# larrow.net
KiCad netlist of a schematic drawn in EAGLE
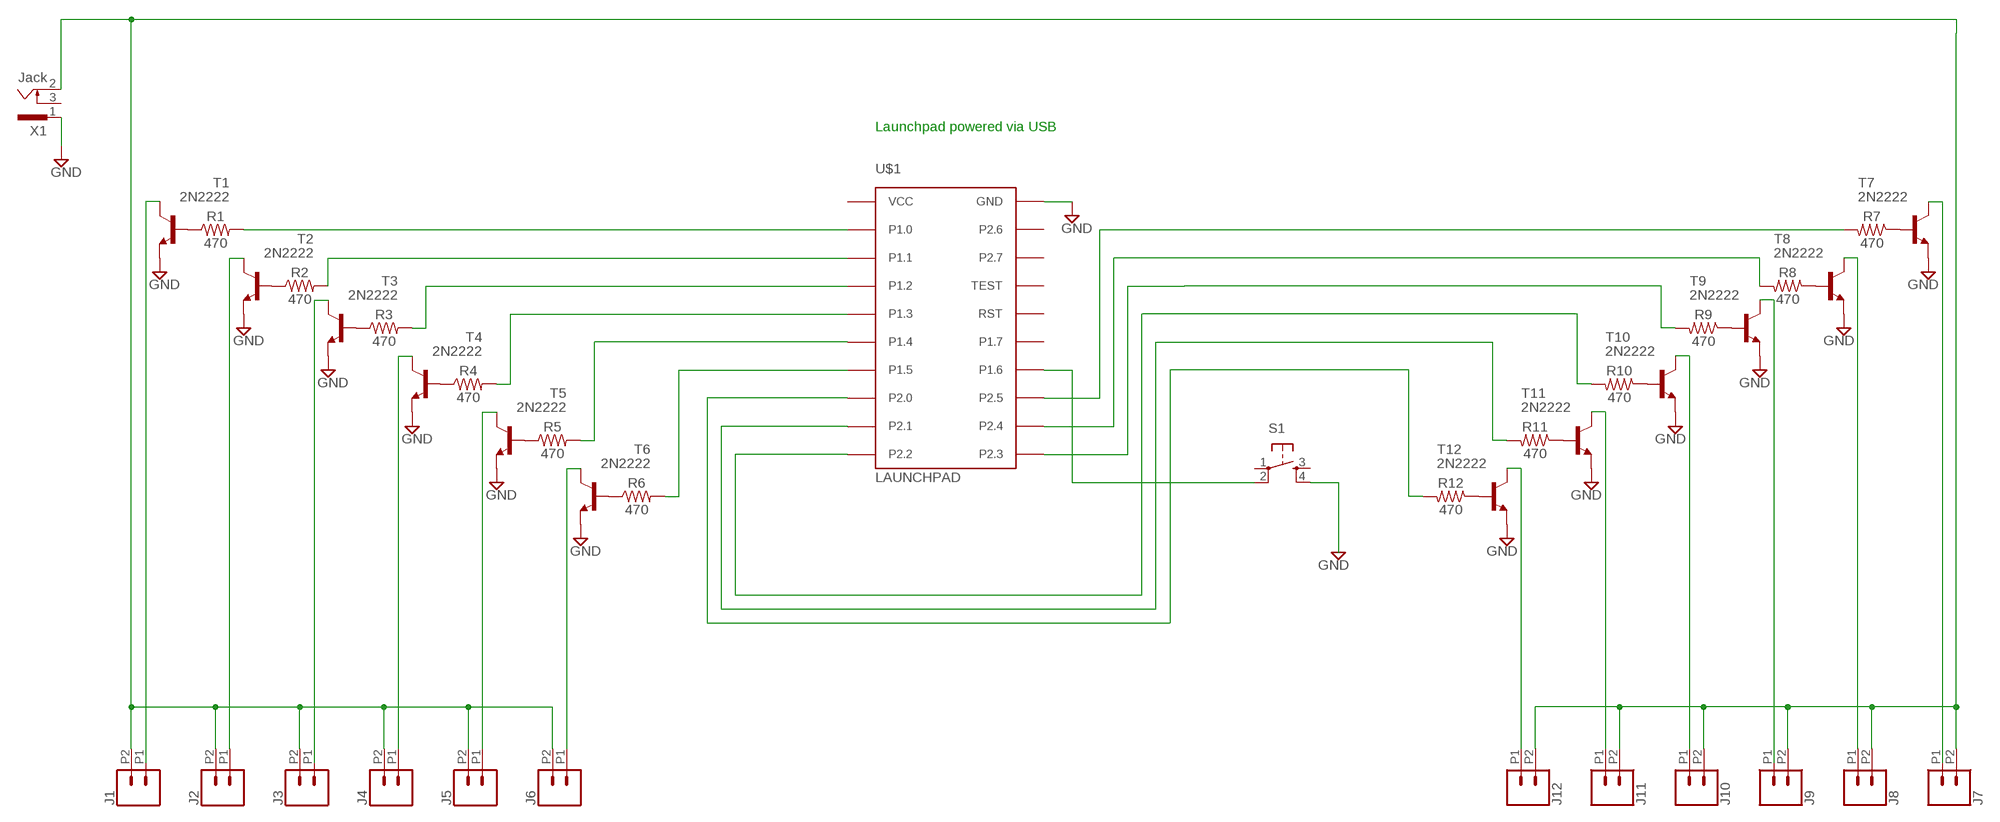
[diagram p0: schematic, sheet 1]

(export (version "E")
  (design (tool "Eeschema 10.0.6"))
  (components
    (comp (ref "J1")
      (value "CONN_022.54MM_SCREWTERM")
      (footprint "eagle-import:1X02_2.54_SCREWTERM")
      (libsource (lib "eagle-import") (part "CONN_022.54MM_SCREWTERM"))
    )
    (comp (ref "J2")
      (value "CONN_022.54MM_SCREWTERM")
      (footprint "eagle-import:1X02_2.54_SCREWTERM")
      (libsource (lib "eagle-import") (part "CONN_022.54MM_SCREWTERM"))
    )
    (comp (ref "J3")
      (value "CONN_022.54MM_SCREWTERM")
      (footprint "eagle-import:1X02_2.54_SCREWTERM")
      (libsource (lib "eagle-import") (part "CONN_022.54MM_SCREWTERM"))
    )
    (comp (ref "J4")
      (value "CONN_022.54MM_SCREWTERM")
      (footprint "eagle-import:1X02_2.54_SCREWTERM")
      (libsource (lib "eagle-import") (part "CONN_022.54MM_SCREWTERM"))
    )
    (comp (ref "J5")
      (value "CONN_022.54MM_SCREWTERM")
      (footprint "eagle-import:1X02_2.54_SCREWTERM")
      (libsource (lib "eagle-import") (part "CONN_022.54MM_SCREWTERM"))
    )
    (comp (ref "J6")
      (value "CONN_022.54MM_SCREWTERM")
      (footprint "eagle-import:1X02_2.54_SCREWTERM")
      (libsource (lib "eagle-import") (part "CONN_022.54MM_SCREWTERM"))
    )
    (comp (ref "J7")
      (value "CONN_022.54MM_SCREWTERM")
      (footprint "eagle-import:1X02_2.54_SCREWTERM")
      (libsource (lib "eagle-import") (part "CONN_022.54MM_SCREWTERM"))
    )
    (comp (ref "J8")
      (value "CONN_022.54MM_SCREWTERM")
      (footprint "eagle-import:1X02_2.54_SCREWTERM")
      (libsource (lib "eagle-import") (part "CONN_022.54MM_SCREWTERM"))
    )
    (comp (ref "J9")
      (value "CONN_022.54MM_SCREWTERM")
      (footprint "eagle-import:1X02_2.54_SCREWTERM")
      (libsource (lib "eagle-import") (part "CONN_022.54MM_SCREWTERM"))
    )
    (comp (ref "J10")
      (value "CONN_022.54MM_SCREWTERM")
      (footprint "eagle-import:1X02_2.54_SCREWTERM")
      (libsource (lib "eagle-import") (part "CONN_022.54MM_SCREWTERM"))
    )
    (comp (ref "J11")
      (value "CONN_022.54MM_SCREWTERM")
      (footprint "eagle-import:1X02_2.54_SCREWTERM")
      (libsource (lib "eagle-import") (part "CONN_022.54MM_SCREWTERM"))
    )
    (comp (ref "J12")
      (value "CONN_022.54MM_SCREWTERM")
      (footprint "eagle-import:1X02_2.54_SCREWTERM")
      (libsource (lib "eagle-import") (part "CONN_022.54MM_SCREWTERM"))
    )
    (comp (ref "R1")
      (value "470")
      (footprint "eagle-import:AXIAL-0.3")
      (libsource (lib "eagle-import") (part "1KOHM-HORIZ-1/4W-1%"))
    )
    (comp (ref "R2")
      (value "470")
      (footprint "eagle-import:AXIAL-0.3")
      (libsource (lib "eagle-import") (part "1KOHM-HORIZ-1/4W-1%"))
    )
    (comp (ref "R3")
      (value "470")
      (footprint "eagle-import:AXIAL-0.3")
      (libsource (lib "eagle-import") (part "1KOHM-HORIZ-1/4W-1%"))
    )
    (comp (ref "R4")
      (value "470")
      (footprint "eagle-import:AXIAL-0.3")
      (libsource (lib "eagle-import") (part "1KOHM-HORIZ-1/4W-1%"))
    )
    (comp (ref "R5")
      (value "470")
      (footprint "eagle-import:AXIAL-0.3")
      (libsource (lib "eagle-import") (part "1KOHM-HORIZ-1/4W-1%"))
    )
    (comp (ref "R6")
      (value "470")
      (footprint "eagle-import:AXIAL-0.3")
      (libsource (lib "eagle-import") (part "1KOHM-HORIZ-1/4W-1%"))
    )
    (comp (ref "R7")
      (value "470")
      (footprint "eagle-import:AXIAL-0.3")
      (libsource (lib "eagle-import") (part "1KOHM-HORIZ-1/4W-1%"))
    )
    (comp (ref "R8")
      (value "470")
      (footprint "eagle-import:AXIAL-0.3")
      (libsource (lib "eagle-import") (part "1KOHM-HORIZ-1/4W-1%"))
    )
    (comp (ref "R9")
      (value "470")
      (footprint "eagle-import:AXIAL-0.3")
      (libsource (lib "eagle-import") (part "1KOHM-HORIZ-1/4W-1%"))
    )
    (comp (ref "R10")
      (value "470")
      (footprint "eagle-import:AXIAL-0.3")
      (libsource (lib "eagle-import") (part "1KOHM-HORIZ-1/4W-1%"))
    )
    (comp (ref "R11")
      (value "470")
      (footprint "eagle-import:AXIAL-0.3")
      (libsource (lib "eagle-import") (part "1KOHM-HORIZ-1/4W-1%"))
    )
    (comp (ref "R12")
      (value "470")
      (footprint "eagle-import:AXIAL-0.3")
      (libsource (lib "eagle-import") (part "1KOHM-HORIZ-1/4W-1%"))
    )
    (comp (ref "S1")
      (value "TAC_SWITCHPTH")
      (footprint "eagle-import:TACTILE-PTH")
      (libsource (lib "eagle-import") (part "TAC_SWITCHPTH"))
    )
    (comp (ref "T1")
      (value "2N2222")
      (footprint "eagle-import:TO92-EBC-OVAL")
      (libsource (lib "eagle-import") (part "2N2222"))
    )
    (comp (ref "T2")
      (value "2N2222")
      (footprint "eagle-import:TO92-EBC-OVAL")
      (libsource (lib "eagle-import") (part "2N2222"))
    )
    (comp (ref "T3")
      (value "2N2222")
      (footprint "eagle-import:TO92-EBC-OVAL")
      (libsource (lib "eagle-import") (part "2N2222"))
    )
    (comp (ref "T4")
      (value "2N2222")
      (footprint "eagle-import:TO92-EBC-OVAL")
      (libsource (lib "eagle-import") (part "2N2222"))
    )
    (comp (ref "T5")
      (value "2N2222")
      (footprint "eagle-import:TO92-EBC-OVAL")
      (libsource (lib "eagle-import") (part "2N2222"))
    )
    (comp (ref "T6")
      (value "2N2222")
      (footprint "eagle-import:TO92-EBC-OVAL")
      (libsource (lib "eagle-import") (part "2N2222"))
    )
    (comp (ref "T7")
      (value "2N2222")
      (footprint "eagle-import:TO92-EBC-OVAL")
      (libsource (lib "eagle-import") (part "2N2222"))
    )
    (comp (ref "T8")
      (value "2N2222")
      (footprint "eagle-import:TO92-EBC-OVAL")
      (libsource (lib "eagle-import") (part "2N2222"))
    )
    (comp (ref "T9")
      (value "2N2222")
      (footprint "eagle-import:TO92-EBC-OVAL")
      (libsource (lib "eagle-import") (part "2N2222"))
    )
    (comp (ref "T10")
      (value "2N2222")
      (footprint "eagle-import:TO92-EBC-OVAL")
      (libsource (lib "eagle-import") (part "2N2222"))
    )
    (comp (ref "T11")
      (value "2N2222")
      (footprint "eagle-import:TO92-EBC-OVAL")
      (libsource (lib "eagle-import") (part "2N2222"))
    )
    (comp (ref "T12")
      (value "2N2222")
      (footprint "eagle-import:TO92-EBC-OVAL")
      (libsource (lib "eagle-import") (part "2N2222"))
    )
    (comp (ref "U$1")
      (value "LAUNCHPAD")
      (footprint "eagle-import:LAUNCHPAD")
      (libsource (lib "eagle-import") (part "LAUNCHPAD"))
    )
    (comp (ref "X1")
      (value "Jack")
      (footprint "eagle-import:SCD-014-A")
      (libsource (lib "eagle-import") (part "SCD-014A"))
    )
  )
  (nets
    (net (code "1") (name "/VCC") (class "Default")
      (node (ref "U$1") (pin "VCC") (pinfunction "VCC_VCC") (pintype "power_in"))
    )
    (net (code "2") (name "GND") (class "Default")
      (node (ref "S1") (pin "4") (pinfunction "4_4") (pintype "passive"))
      (node (ref "T1") (pin "E") (pinfunction "E_E") (pintype "passive"))
      (node (ref "T10") (pin "E") (pinfunction "E_E") (pintype "passive"))
      (node (ref "T11") (pin "E") (pinfunction "E_E") (pintype "passive"))
      (node (ref "T12") (pin "E") (pinfunction "E_E") (pintype "passive"))
      (node (ref "T2") (pin "E") (pinfunction "E_E") (pintype "passive"))
      (node (ref "T3") (pin "E") (pinfunction "E_E") (pintype "passive"))
      (node (ref "T4") (pin "E") (pinfunction "E_E") (pintype "passive"))
      (node (ref "T5") (pin "E") (pinfunction "E_E") (pintype "passive"))
      (node (ref "T6") (pin "E") (pinfunction "E_E") (pintype "passive"))
      (node (ref "T7") (pin "E") (pinfunction "E_E") (pintype "passive"))
      (node (ref "T8") (pin "E") (pinfunction "E_E") (pintype "passive"))
      (node (ref "T9") (pin "E") (pinfunction "E_E") (pintype "passive"))
      (node (ref "U$1") (pin "GND") (pinfunction "GND_GND") (pintype "power_in"))
      (node (ref "X1") (pin "1") (pinfunction "1_1") (pintype "passive"))
    )
    (net (code "3") (name "Net-(J1-1)") (class "Default")
      (node (ref "J1") (pin "P1") (pinfunction "1_P1") (pintype "passive"))
      (node (ref "T1") (pin "C") (pinfunction "C_C") (pintype "passive"))
    )
    (net (code "4") (name "Net-(J1-2)") (class "Default")
      (node (ref "J1") (pin "P2") (pinfunction "2_P2") (pintype "passive"))
      (node (ref "J10") (pin "P2") (pinfunction "2_P2") (pintype "passive"))
      (node (ref "J11") (pin "P2") (pinfunction "2_P2") (pintype "passive"))
      (node (ref "J12") (pin "P2") (pinfunction "2_P2") (pintype "passive"))
      (node (ref "J2") (pin "P2") (pinfunction "2_P2") (pintype "passive"))
      (node (ref "J3") (pin "P2") (pinfunction "2_P2") (pintype "passive"))
      (node (ref "J4") (pin "P2") (pinfunction "2_P2") (pintype "passive"))
      (node (ref "J5") (pin "P2") (pinfunction "2_P2") (pintype "passive"))
      (node (ref "J6") (pin "P2") (pinfunction "2_P2") (pintype "passive"))
      (node (ref "J7") (pin "P2") (pinfunction "2_P2") (pintype "passive"))
      (node (ref "J8") (pin "P2") (pinfunction "2_P2") (pintype "passive"))
      (node (ref "J9") (pin "P2") (pinfunction "2_P2") (pintype "passive"))
      (node (ref "X1") (pin "2") (pinfunction "2_2") (pintype "passive"))
    )
    (net (code "5") (name "Net-(J2-1)") (class "Default")
      (node (ref "J2") (pin "P1") (pinfunction "1_P1") (pintype "passive"))
      (node (ref "T2") (pin "C") (pinfunction "C_C") (pintype "passive"))
    )
    (net (code "6") (name "Net-(J3-1)") (class "Default")
      (node (ref "J3") (pin "P1") (pinfunction "1_P1") (pintype "passive"))
      (node (ref "T3") (pin "C") (pinfunction "C_C") (pintype "passive"))
    )
    (net (code "7") (name "Net-(J4-1)") (class "Default")
      (node (ref "J4") (pin "P1") (pinfunction "1_P1") (pintype "passive"))
      (node (ref "T4") (pin "C") (pinfunction "C_C") (pintype "passive"))
    )
    (net (code "8") (name "Net-(J5-1)") (class "Default")
      (node (ref "J5") (pin "P1") (pinfunction "1_P1") (pintype "passive"))
      (node (ref "T5") (pin "C") (pinfunction "C_C") (pintype "passive"))
    )
    (net (code "9") (name "Net-(J6-1)") (class "Default")
      (node (ref "J6") (pin "P1") (pinfunction "1_P1") (pintype "passive"))
      (node (ref "T6") (pin "C") (pinfunction "C_C") (pintype "passive"))
    )
    (net (code "10") (name "Net-(J7-1)") (class "Default")
      (node (ref "J7") (pin "P1") (pinfunction "1_P1") (pintype "passive"))
      (node (ref "T7") (pin "C") (pinfunction "C_C") (pintype "passive"))
    )
    (net (code "11") (name "Net-(J8-1)") (class "Default")
      (node (ref "J8") (pin "P1") (pinfunction "1_P1") (pintype "passive"))
      (node (ref "T8") (pin "C") (pinfunction "C_C") (pintype "passive"))
    )
    (net (code "12") (name "Net-(J9-1)") (class "Default")
      (node (ref "J9") (pin "P1") (pinfunction "1_P1") (pintype "passive"))
      (node (ref "T9") (pin "C") (pinfunction "C_C") (pintype "passive"))
    )
    (net (code "13") (name "Net-(J10-1)") (class "Default")
      (node (ref "J10") (pin "P1") (pinfunction "1_P1") (pintype "passive"))
      (node (ref "T10") (pin "C") (pinfunction "C_C") (pintype "passive"))
    )
    (net (code "14") (name "Net-(J11-1)") (class "Default")
      (node (ref "J11") (pin "P1") (pinfunction "1_P1") (pintype "passive"))
      (node (ref "T11") (pin "C") (pinfunction "C_C") (pintype "passive"))
    )
    (net (code "15") (name "Net-(J12-1)") (class "Default")
      (node (ref "J12") (pin "P1") (pinfunction "1_P1") (pintype "passive"))
      (node (ref "T12") (pin "C") (pinfunction "C_C") (pintype "passive"))
    )
    (net (code "16") (name "Net-(R1-1)") (class "Default")
      (node (ref "R1") (pin "P$1") (pinfunction "1_P$1") (pintype "passive"))
      (node (ref "T1") (pin "B") (pinfunction "B_B") (pintype "passive"))
    )
    (net (code "17") (name "Net-(R1-2)") (class "Default")
      (node (ref "R1") (pin "P$2") (pinfunction "2_P$2") (pintype "passive"))
      (node (ref "U$1") (pin "P1.0") (pinfunction "P1.0_P1.0") (pintype "bidirectional"))
    )
    (net (code "18") (name "Net-(R2-1)") (class "Default")
      (node (ref "R2") (pin "P$1") (pinfunction "1_P$1") (pintype "passive"))
      (node (ref "T2") (pin "B") (pinfunction "B_B") (pintype "passive"))
    )
    (net (code "19") (name "Net-(R2-2)") (class "Default")
      (node (ref "R2") (pin "P$2") (pinfunction "2_P$2") (pintype "passive"))
      (node (ref "U$1") (pin "P1.1") (pinfunction "P1.1_P1.1") (pintype "bidirectional"))
    )
    (net (code "20") (name "Net-(R3-1)") (class "Default")
      (node (ref "R3") (pin "P$1") (pinfunction "1_P$1") (pintype "passive"))
      (node (ref "T3") (pin "B") (pinfunction "B_B") (pintype "passive"))
    )
    (net (code "21") (name "Net-(R3-2)") (class "Default")
      (node (ref "R3") (pin "P$2") (pinfunction "2_P$2") (pintype "passive"))
      (node (ref "U$1") (pin "P1.2") (pinfunction "P1.2_P1.2") (pintype "bidirectional"))
    )
    (net (code "22") (name "Net-(R4-1)") (class "Default")
      (node (ref "R4") (pin "P$1") (pinfunction "1_P$1") (pintype "passive"))
      (node (ref "T4") (pin "B") (pinfunction "B_B") (pintype "passive"))
    )
    (net (code "23") (name "Net-(R4-2)") (class "Default")
      (node (ref "R4") (pin "P$2") (pinfunction "2_P$2") (pintype "passive"))
      (node (ref "U$1") (pin "P1.3") (pinfunction "P1.3_P1.3") (pintype "bidirectional"))
    )
    (net (code "24") (name "Net-(R5-1)") (class "Default")
      (node (ref "R5") (pin "P$1") (pinfunction "1_P$1") (pintype "passive"))
      (node (ref "T5") (pin "B") (pinfunction "B_B") (pintype "passive"))
    )
    (net (code "25") (name "Net-(R5-2)") (class "Default")
      (node (ref "R5") (pin "P$2") (pinfunction "2_P$2") (pintype "passive"))
      (node (ref "U$1") (pin "P1.4") (pinfunction "P1.4_P1.4") (pintype "bidirectional"))
    )
    (net (code "26") (name "Net-(R6-1)") (class "Default")
      (node (ref "R6") (pin "P$1") (pinfunction "1_P$1") (pintype "passive"))
      (node (ref "T6") (pin "B") (pinfunction "B_B") (pintype "passive"))
    )
    (net (code "27") (name "Net-(R6-2)") (class "Default")
      (node (ref "R6") (pin "P$2") (pinfunction "2_P$2") (pintype "passive"))
      (node (ref "U$1") (pin "P1.5") (pinfunction "P1.5_P1.5") (pintype "bidirectional"))
    )
    (net (code "28") (name "Net-(R7-1)") (class "Default")
      (node (ref "R7") (pin "P$1") (pinfunction "1_P$1") (pintype "passive"))
      (node (ref "T7") (pin "B") (pinfunction "B_B") (pintype "passive"))
    )
    (net (code "29") (name "Net-(R7-2)") (class "Default")
      (node (ref "R7") (pin "P$2") (pinfunction "2_P$2") (pintype "passive"))
      (node (ref "U$1") (pin "P2.5") (pinfunction "P2.5_P2.5") (pintype "bidirectional"))
    )
    (net (code "30") (name "Net-(R8-1)") (class "Default")
      (node (ref "R8") (pin "P$1") (pinfunction "1_P$1") (pintype "passive"))
      (node (ref "T8") (pin "B") (pinfunction "B_B") (pintype "passive"))
    )
    (net (code "31") (name "Net-(R8-2)") (class "Default")
      (node (ref "R8") (pin "P$2") (pinfunction "2_P$2") (pintype "passive"))
      (node (ref "U$1") (pin "P2.4") (pinfunction "P2.4_P2.4") (pintype "bidirectional"))
    )
    (net (code "32") (name "Net-(R9-1)") (class "Default")
      (node (ref "R9") (pin "P$1") (pinfunction "1_P$1") (pintype "passive"))
      (node (ref "T9") (pin "B") (pinfunction "B_B") (pintype "passive"))
    )
    (net (code "33") (name "Net-(R9-2)") (class "Default")
      (node (ref "R9") (pin "P$2") (pinfunction "2_P$2") (pintype "passive"))
      (node (ref "U$1") (pin "P2.3") (pinfunction "P2.3_P2.3") (pintype "bidirectional"))
    )
    (net (code "34") (name "Net-(R10-1)") (class "Default")
      (node (ref "R10") (pin "P$1") (pinfunction "1_P$1") (pintype "passive"))
      (node (ref "T10") (pin "B") (pinfunction "B_B") (pintype "passive"))
    )
    (net (code "35") (name "Net-(R10-2)") (class "Default")
      (node (ref "R10") (pin "P$2") (pinfunction "2_P$2") (pintype "passive"))
      (node (ref "U$1") (pin "P2.2") (pinfunction "P2.2_P2.2") (pintype "bidirectional"))
    )
    (net (code "36") (name "Net-(R11-1)") (class "Default")
      (node (ref "R11") (pin "P$1") (pinfunction "1_P$1") (pintype "passive"))
      (node (ref "T11") (pin "B") (pinfunction "B_B") (pintype "passive"))
    )
    (net (code "37") (name "Net-(R11-2)") (class "Default")
      (node (ref "R11") (pin "P$2") (pinfunction "2_P$2") (pintype "passive"))
      (node (ref "U$1") (pin "P2.1") (pinfunction "P2.1_P2.1") (pintype "bidirectional"))
    )
    (net (code "38") (name "Net-(R12-1)") (class "Default")
      (node (ref "R12") (pin "P$1") (pinfunction "1_P$1") (pintype "passive"))
      (node (ref "T12") (pin "B") (pinfunction "B_B") (pintype "passive"))
    )
    (net (code "39") (name "Net-(R12-2)") (class "Default")
      (node (ref "R12") (pin "P$2") (pinfunction "2_P$2") (pintype "passive"))
      (node (ref "U$1") (pin "P2.0") (pinfunction "P2.0_P2.0") (pintype "bidirectional"))
    )
    (net (code "40") (name "Net-(S1-Pad2)") (class "Default")
      (node (ref "S1") (pin "2") (pinfunction "2_2") (pintype "passive"))
      (node (ref "U$1") (pin "P1.6") (pinfunction "P1.6_P1.6") (pintype "bidirectional"))
    )
    (net (code "41") (name "unconnected-(S1-Pad1)") (class "Default")
      (node (ref "S1") (pin "1") (pinfunction "1_1") (pintype "passive"))
    )
    (net (code "42") (name "unconnected-(S1-Pad3)") (class "Default")
      (node (ref "S1") (pin "3") (pinfunction "3_3") (pintype "passive"))
    )
    (net (code "43") (name "unconnected-(U$1-PadP1.7)") (class "Default")
      (node (ref "U$1") (pin "P1.7") (pinfunction "P1.7_P1.7") (pintype "bidirectional"))
    )
    (net (code "44") (name "unconnected-(U$1-PadP2.6)") (class "Default")
      (node (ref "U$1") (pin "P2.6") (pinfunction "P2.6_P2.6") (pintype "bidirectional"))
    )
    (net (code "45") (name "unconnected-(U$1-PadP2.7)") (class "Default")
      (node (ref "U$1") (pin "P2.7") (pinfunction "P2.7_P2.7") (pintype "bidirectional"))
    )
    (net (code "46") (name "unconnected-(U$1-PadRST)") (class "Default")
      (node (ref "U$1") (pin "RST") (pinfunction "RST_RST") (pintype "bidirectional"))
    )
    (net (code "47") (name "unconnected-(U$1-PadTEST)") (class "Default")
      (node (ref "U$1") (pin "TEST") (pinfunction "TEST_TEST") (pintype "bidirectional"))
    )
    (net (code "48") (name "unconnected-(X1-Pad3)") (class "Default")
      (node (ref "X1") (pin "3") (pinfunction "3_3") (pintype "passive"))
    )
  )
)
